# RS485_block.net
KiCad netlist of a schematic drawn in Altium Designer
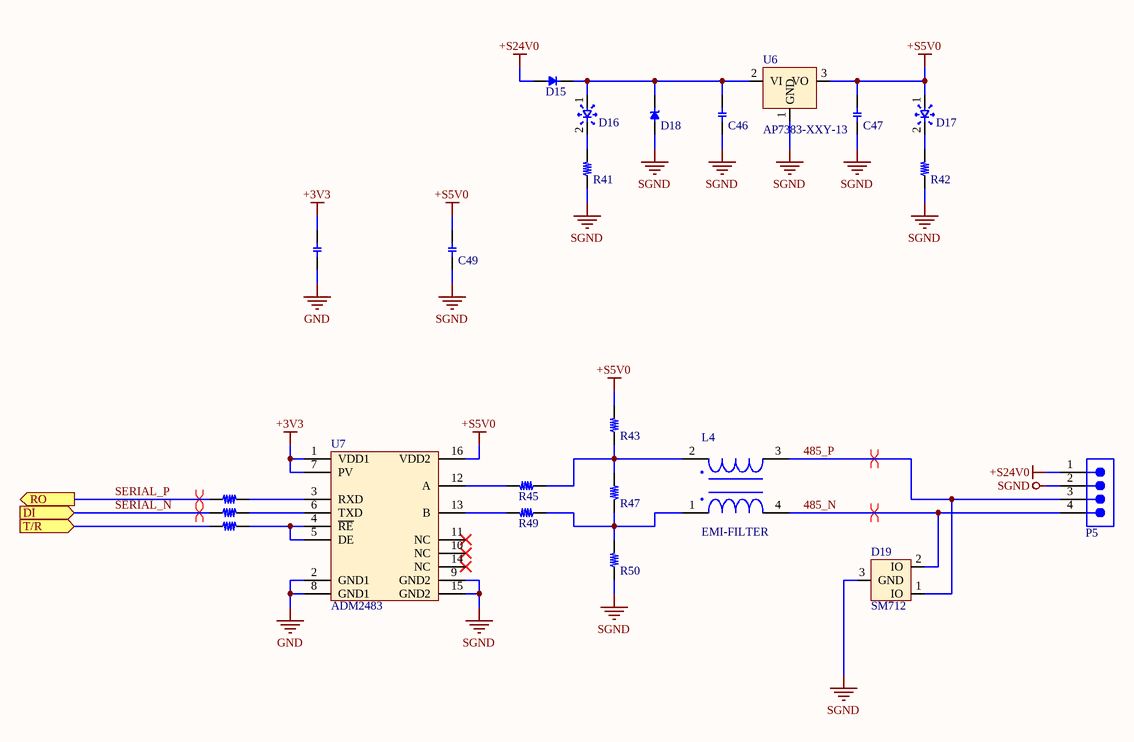
[diagram p0: RS485_block.SchDoc]

(export (version "E")
  (design (tool "Eeschema 10.0.6"))
  (components
    (comp (ref "C46")
      (value "CAP_SMD")
      (footprint "C 0603")
      (libsource (lib "radmehr_library") (part "CAP_SMD"))
    )
    (comp (ref "C47")
      (value "CAP_SMD")
      (footprint "C 0603")
      (libsource (lib "radmehr_library") (part "CAP_SMD"))
    )
    (comp (ref "C48")
      (value "CAP_SMD")
      (footprint "C 0603")
      (libsource (lib "radmehr_library") (part "CAP_SMD"))
    )
    (comp (ref "C49")
      (value "CAP_SMD")
      (footprint "C 0603")
      (libsource (lib "radmehr_library") (part "CAP_SMD"))
    )
    (comp (ref "D15")
      (value "DIOD_SMD")
      (footprint "DIOD_SMA")
      (libsource (lib "radmehr_library") (part "DIOD_SMD"))
    )
    (comp (ref "D16")
      (value "LED_SMD")
      (footprint "D 0603")
      (libsource (lib "radmehr_library") (part "LED_SMD"))
    )
    (comp (ref "D17")
      (value "LED_SMD")
      (footprint "D 0603")
      (libsource (lib "radmehr_library") (part "LED_SMD"))
    )
    (comp (ref "D18")
      (value "TVS_UI")
      (footprint "DIOD_SMB")
      (libsource (lib "radmehr_library") (part "DIOD_SMD_TVS_UI"))
    )
    (comp (ref "D19")
      (value "SM712")
      (footprint "SOT-23_3_D")
      (libsource (lib "radmehr_library") (part "SM712"))
    )
    (comp (ref "L4")
      (value "EMI-FILTER")
      (footprint "EMI-FILTER-1206")
      (libsource (lib "radmehr_library") (part "EMI-FILTER"))
    )
    (comp (ref "P5")
      (value "691321300004")
      (footprint "691321300004")
      (description "WR-TBL Series 321 Vertical PCB Header, Through Hole, pitch 3.81mm, 4p")
      (fields (field (name "MANUFACTURER") "Wurth Elektronik"))
      (libsource (lib "Altium_WR-TBL (rev22a)") (part "691321300004"))
    )
    (comp (ref "R41")
      (value "RES_SMD")
      (footprint "R 0603")
      (libsource (lib "radmehr_library") (part "RES_SMD"))
    )
    (comp (ref "R42")
      (value "RES_SMD")
      (footprint "R 0603")
      (libsource (lib "radmehr_library") (part "RES_SMD"))
    )
    (comp (ref "R43")
      (value "RES_SMD")
      (footprint "R 1206")
      (libsource (lib "radmehr_library") (part "RES_SMD"))
    )
    (comp (ref "R44")
      (value "RES_SMD")
      (footprint "R 0603")
      (libsource (lib "radmehr_library") (part "RES_SMD"))
    )
    (comp (ref "R45")
      (value "RES_SMD")
      (footprint "R 1206")
      (libsource (lib "radmehr_library") (part "RES_SMD"))
    )
    (comp (ref "R46")
      (value "RES_SMD")
      (footprint "R 0603")
      (libsource (lib "radmehr_library") (part "RES_SMD"))
    )
    (comp (ref "R47")
      (value "RES_SMD")
      (footprint "R 1206")
      (libsource (lib "radmehr_library") (part "RES_SMD"))
    )
    (comp (ref "R48")
      (value "RES_SMD")
      (footprint "R 0603")
      (libsource (lib "radmehr_library") (part "RES_SMD"))
    )
    (comp (ref "R49")
      (value "RES_SMD")
      (footprint "R 1206")
      (libsource (lib "radmehr_library") (part "RES_SMD"))
    )
    (comp (ref "R50")
      (value "RES_SMD")
      (footprint "R 1206")
      (libsource (lib "radmehr_library") (part "RES_SMD"))
    )
    (comp (ref "U6")
      (value "AP7383-XXY-13")
      (footprint "SOT89-U")
      (libsource (lib "radmehr_library") (part "AP7383-XXY-13"))
    )
    (comp (ref "U7")
      (value "ADM2483")
      (footprint "SOIC-16-WIDE")
      (libsource (lib "radmehr_library") (part "ADM2483"))
    )
  )
  (nets
    (net (code "1") (name "+3V3") (class "Default")
      (node (ref "C48") (pin "2") (pinfunction "2_2") (pintype "passive"))
      (node (ref "U7") (pin "1") (pinfunction "VDD1_1") (pintype "passive"))
      (node (ref "U7") (pin "7") (pinfunction "PV_7") (pintype "passive"))
    )
    (net (code "2") (name "+S5V0") (class "Default")
      (node (ref "C47") (pin "2") (pinfunction "2_2") (pintype "passive"))
      (node (ref "C49") (pin "2") (pinfunction "2_2") (pintype "passive"))
      (node (ref "D17") (pin "1") (pintype "passive"))
      (node (ref "R43") (pin "2") (pinfunction "2_2") (pintype "passive"))
      (node (ref "U6") (pin "3") (pinfunction "VO_3") (pintype "passive"))
      (node (ref "U7") (pin "16") (pinfunction "VDD2_16") (pintype "passive"))
    )
    (net (code "3") (name "+S24V0") (class "Default")
      (node (ref "D15") (pin "1") (pinfunction "1_1") (pintype "passive"))
      (node (ref "P5") (pin "1") (pinfunction "1_1") (pintype "passive"))
    )
    (net (code "4") (name "/485_N") (class "Default")
      (node (ref "D19") (pin "2") (pinfunction "IO_2") (pintype "passive"))
      (node (ref "L4") (pin "4") (pinfunction "4_4") (pintype "power_in"))
      (node (ref "P5") (pin "4") (pinfunction "4_4") (pintype "passive"))
    )
    (net (code "5") (name "/485_P") (class "Default")
      (node (ref "D19") (pin "1") (pinfunction "IO_1") (pintype "passive"))
      (node (ref "L4") (pin "3") (pinfunction "3_3") (pintype "power_in"))
      (node (ref "P5") (pin "3") (pinfunction "3_3") (pintype "passive"))
    )
    (net (code "6") (name "/SERIAL_N") (class "Default")
      (node (ref "R46") (pin "1") (pinfunction "1_1") (pintype "passive"))
    )
    (net (code "7") (name "/SERIAL_P") (class "Default")
      (node (ref "R44") (pin "1") (pinfunction "1_1") (pintype "passive"))
    )
    (net (code "8") (name "/T{slash}R") (class "Default")
      (node (ref "R48") (pin "1") (pinfunction "1_1") (pintype "passive"))
    )
    (net (code "9") (name "GND") (class "Default")
      (node (ref "C48") (pin "1") (pinfunction "1_1") (pintype "passive"))
      (node (ref "U7") (pin "2") (pinfunction "GND1_2") (pintype "passive"))
      (node (ref "U7") (pin "8") (pinfunction "GND1_8") (pintype "passive"))
    )
    (net (code "10") (name "Net-(D16-Pad2)") (class "Default")
      (node (ref "D16") (pin "2") (pintype "passive"))
      (node (ref "R41") (pin "2") (pinfunction "2_2") (pintype "passive"))
    )
    (net (code "11") (name "Net-(D17-Pad2)") (class "Default")
      (node (ref "D17") (pin "2") (pintype "passive"))
      (node (ref "R42") (pin "2") (pinfunction "2_2") (pintype "passive"))
    )
    (net (code "12") (name "Net-(L4-Pad1)") (class "Default")
      (node (ref "L4") (pin "1") (pinfunction "1_1") (pintype "power_in"))
      (node (ref "R47") (pin "2") (pinfunction "2_2") (pintype "passive"))
      (node (ref "R49") (pin "1") (pinfunction "1_1") (pintype "passive"))
      (node (ref "R50") (pin "2") (pinfunction "2_2") (pintype "passive"))
    )
    (net (code "13") (name "Net-(L4-Pad2)") (class "Default")
      (node (ref "L4") (pin "2") (pinfunction "2_2") (pintype "power_in"))
      (node (ref "R43") (pin "1") (pinfunction "1_1") (pintype "passive"))
      (node (ref "R45") (pin "1") (pinfunction "1_1") (pintype "passive"))
      (node (ref "R47") (pin "1") (pinfunction "1_1") (pintype "passive"))
    )
    (net (code "14") (name "Net-(U6-VI)") (class "Default")
      (node (ref "C46") (pin "2") (pinfunction "2_2") (pintype "passive"))
      (node (ref "D15") (pin "2") (pinfunction "2_2") (pintype "passive"))
      (node (ref "D16") (pin "1") (pintype "passive"))
      (node (ref "D18") (pin "2") (pinfunction "2_2") (pintype "passive"))
      (node (ref "U6") (pin "2") (pinfunction "VI_2") (pintype "passive"))
    )
    (net (code "15") (name "Net-(U7-A)") (class "Default")
      (node (ref "R45") (pin "2") (pinfunction "2_2") (pintype "passive"))
      (node (ref "U7") (pin "12") (pinfunction "A_12") (pintype "passive"))
    )
    (net (code "16") (name "Net-(U7-B)") (class "Default")
      (node (ref "R49") (pin "2") (pinfunction "2_2") (pintype "passive"))
      (node (ref "U7") (pin "13") (pinfunction "B_13") (pintype "passive"))
    )
    (net (code "17") (name "Net-(U7-DE)") (class "Default")
      (node (ref "R48") (pin "2") (pinfunction "2_2") (pintype "passive"))
      (node (ref "U7") (pin "4") (pinfunction "~{RE}_4") (pintype "passive"))
      (node (ref "U7") (pin "5") (pinfunction "DE_5") (pintype "passive"))
    )
    (net (code "18") (name "Net-(U7-RXD)") (class "Default")
      (node (ref "R44") (pin "2") (pinfunction "2_2") (pintype "passive"))
      (node (ref "U7") (pin "3") (pinfunction "RXD_3") (pintype "passive"))
    )
    (net (code "19") (name "Net-(U7-TXD)") (class "Default")
      (node (ref "R46") (pin "2") (pinfunction "2_2") (pintype "passive"))
      (node (ref "U7") (pin "6") (pinfunction "TXD_6") (pintype "passive"))
    )
    (net (code "20") (name "SGND") (class "Default")
      (node (ref "C46") (pin "1") (pinfunction "1_1") (pintype "passive"))
      (node (ref "C47") (pin "1") (pinfunction "1_1") (pintype "passive"))
      (node (ref "C49") (pin "1") (pinfunction "1_1") (pintype "passive"))
      (node (ref "D18") (pin "1") (pinfunction "1_1") (pintype "passive"))
      (node (ref "D19") (pin "3") (pinfunction "GND_3") (pintype "passive"))
      (node (ref "P5") (pin "2") (pinfunction "2_2") (pintype "passive"))
      (node (ref "R41") (pin "1") (pinfunction "1_1") (pintype "passive"))
      (node (ref "R42") (pin "1") (pinfunction "1_1") (pintype "passive"))
      (node (ref "R50") (pin "1") (pinfunction "1_1") (pintype "passive"))
      (node (ref "U6") (pin "1") (pinfunction "GND_1") (pintype "passive"))
      (node (ref "U7") (pin "15") (pinfunction "GND2_15") (pintype "passive"))
      (node (ref "U7") (pin "9") (pinfunction "GND2_9") (pintype "passive"))
    )
    (net (code "21") (name "unconnected-(U7-NC-Pad10)") (class "Default")
      (node (ref "U7") (pin "10") (pinfunction "NC_10") (pintype "passive+no_connect"))
    )
    (net (code "22") (name "unconnected-(U7-NC-Pad11)") (class "Default")
      (node (ref "U7") (pin "11") (pinfunction "NC_11") (pintype "passive+no_connect"))
    )
    (net (code "23") (name "unconnected-(U7-NC-Pad14)") (class "Default")
      (node (ref "U7") (pin "14") (pinfunction "NC_14") (pintype "passive+no_connect"))
    )
  )
)
